# 1_PowerSupply.net
KiCad netlist of a schematic drawn in Altium Designer
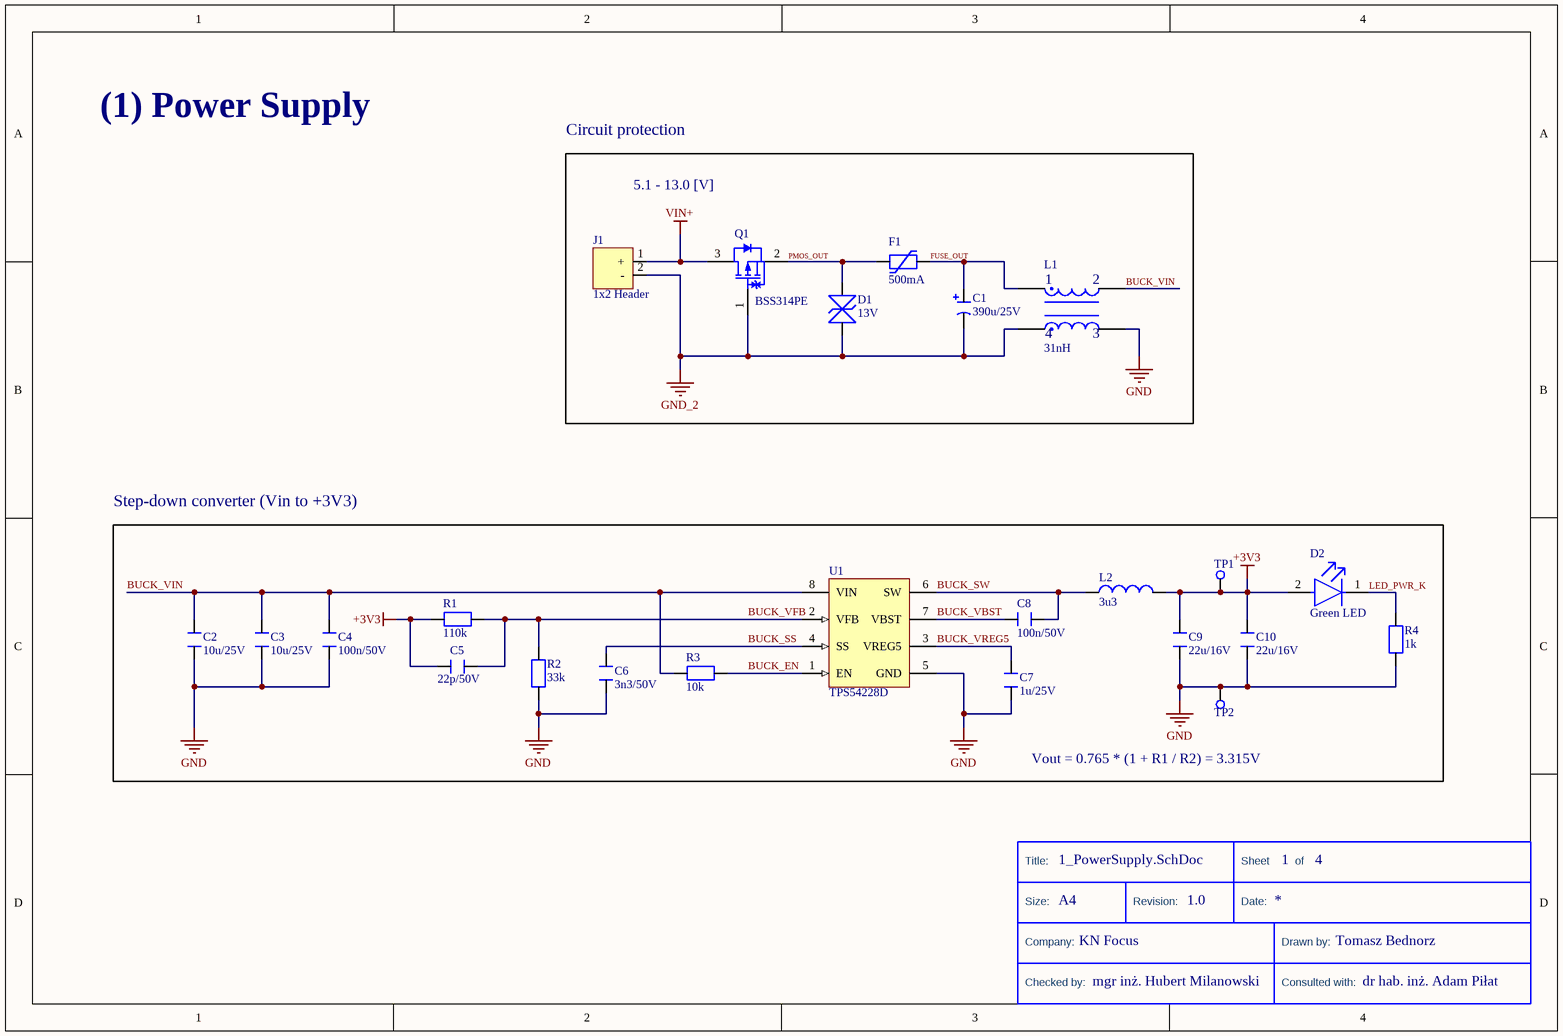
[diagram p0: 1_PowerSupply.SchDoc]

(export (version "E")
  (design (tool "Eeschema 10.0.6"))
  (components
    (comp (ref "C1")
      (value "390u/25V")
      (footprint "CAP_ELECTROLYTIC D8")
      (description "CAP_ELECTROLYTIC D8")
      (libsource (lib "SymbolLib") (part "CAP_ELECTROLYTIC D8"))
    )
    (comp (ref "C2")
      (value "10u/25V")
      (footprint "CAP_1206")
      (description "Generic 1206/3216 capacitor")
      (libsource (lib "SymbolLib") (part "CAP_1206"))
    )
    (comp (ref "C3")
      (value "10u/25V")
      (footprint "CAP_1206")
      (description "Generic 1206/3216 capacitor")
      (libsource (lib "SymbolLib") (part "CAP_1206"))
    )
    (comp (ref "C4")
      (value "100n/50V")
      (footprint "CAP_1206")
      (description "Generic 1206/3216 capacitor")
      (libsource (lib "SymbolLib") (part "CAP_1206"))
    )
    (comp (ref "C5")
      (value "22p/50V")
      (footprint "CAP_1206")
      (description "Generic 1206/3216 capacitor")
      (libsource (lib "SymbolLib") (part "CAP_1206"))
    )
    (comp (ref "C6")
      (value "3n3/50V")
      (footprint "CAP_1206")
      (description "Generic 1206/3216 capacitor")
      (libsource (lib "SymbolLib") (part "CAP_1206"))
    )
    (comp (ref "C7")
      (value "1u/25V")
      (footprint "CAP_1206")
      (description "Generic 1206/3216 capacitor")
      (libsource (lib "SymbolLib") (part "CAP_1206"))
    )
    (comp (ref "C8")
      (value "100n/50V")
      (footprint "CAP_1206")
      (description "Generic 1206/3216 capacitor")
      (libsource (lib "SymbolLib") (part "CAP_1206"))
    )
    (comp (ref "C9")
      (value "22u/16V")
      (footprint "CAP_1206")
      (description "Generic 1206/3216 capacitor")
      (libsource (lib "SymbolLib") (part "CAP_1206"))
    )
    (comp (ref "C10")
      (value "22u/16V")
      (footprint "CAP_1206")
      (description "Generic 1206/3216 capacitor")
      (libsource (lib "SymbolLib") (part "CAP_1206"))
    )
    (comp (ref "D1")
      (value "13V")
      (footprint "TVS_Littlefuse")
      (description "TVS Diode TVS_SMAJ13CA  13V Bidirectional")
      (libsource (lib "SymbolLib") (part "TVS_13V"))
    )
    (comp (ref "D2")
      (value "Green LED")
      (footprint "FP-LTST-C150KGKT-MFG")
      (description "LED GREEN CLEAR 1206 SMD")
      (libsource (lib "Altium Content Vault") (part "8706943c75ba83719d021d2fdc84c58"))
    )
    (comp (ref "F1")
      (value "500mA")
      (footprint "Fuse_1210")
      (description "FUSE 500mA/16V")
      (libsource (lib "SymbolLib") (part "FUSE_0ZCH0050FF2G"))
    )
    (comp (ref "J1")
      (value "1x2 Header")
      (footprint "1x2 Header (Terminal Block 5.08mm)")
      (description "1x2 Header, Through Hole(Terminal Block 5.08mm)")
      (libsource (lib "SymbolLib") (part "1x2 Header (Terminal Block 5.08mm)"))
    )
    (comp (ref "L1")
      (value "31nH")
      (footprint "CMC-1206USB")
      (description "31nH @ 100MHz 2 Line Common Mode Choke Surface Mount 37 Ohms @ 100MHz 1A DCR 0.1 Ohms")
      (libsource (lib "SymbolLib") (part "CMC-1206USB"))
    )
    (comp (ref "L2")
      (value "3u3")
      (footprint "IND_DJNR5020-3R3-S")
      (libsource (lib "SymbolLib") (part "IND_DJNR5020-3R3-S"))
    )
    (comp (ref "Q1")
      (value "BSS314PE")
      (footprint "INF-PG-SOT23_N")
      (fields (field (name "MANUFACTURER") "Infineon"))
      (libsource (lib "Altium Content Vault") (part "INF-BSS3XXPE-PG-SOT23-3"))
    )
    (comp (ref "R1")
      (value "110k")
      (footprint "RES_1206")
      (description "Generic 1206/3216 resistor")
      (libsource (lib "SymbolLib") (part "RES_1206"))
    )
    (comp (ref "R2")
      (value "33k")
      (footprint "RES_1206")
      (description "Generic 1206/3216 resistor")
      (libsource (lib "SymbolLib") (part "RES_1206"))
    )
    (comp (ref "R3")
      (value "10k")
      (footprint "RES_1206")
      (description "Generic 1206/3216 resistor")
      (libsource (lib "SymbolLib") (part "RES_1206"))
    )
    (comp (ref "R4")
      (value "1k")
      (footprint "RES_1206")
      (description "Generic 1206/3216 resistor")
      (libsource (lib "SymbolLib") (part "RES_1206"))
    )
    (comp (ref "TP1")
      (value "TestPoint Pad 1.0mmx1.0mm")
      (footprint "TestPoint Pad 1.0mmx1.0mm")
      (libsource (lib "SymbolLib") (part "TestPoint Pad 1.0mmx1.0mm"))
    )
    (comp (ref "TP2")
      (value "TestPoint Pad 1.0mmx1.0mm")
      (footprint "TestPoint Pad 1.0mmx1.0mm")
      (libsource (lib "SymbolLib") (part "TestPoint Pad 1.0mmx1.0mm"))
    )
    (comp (ref "U1")
      (value "TPS54228D")
      (footprint "D0008A_L")
      (fields (field (name "MANUFACTURER") "Texas Instruments"))
      (libsource (lib "Altium Content Vault") (part "TI-TPS54228D8"))
    )
  )
  (nets
    (net (code "1") (name "+3V3") (class "Default")
      (node (ref "C10") (pin "1") (pinfunction "1_1") (pintype "passive"))
      (node (ref "C5") (pin "2") (pinfunction "2_2") (pintype "passive"))
      (node (ref "C9") (pin "1") (pinfunction "1_1") (pintype "passive"))
      (node (ref "D2") (pin "2") (pinfunction "A_2") (pintype "passive"))
      (node (ref "L2") (pin "2") (pinfunction "2_2") (pintype "passive"))
      (node (ref "R1") (pin "2") (pinfunction "2_2") (pintype "passive"))
      (node (ref "TP1") (pin "1") (pinfunction "1_1") (pintype "passive"))
    )
    (net (code "2") (name "/BUCK_EN") (class "Default")
      (node (ref "R3") (pin "1") (pinfunction "1_1") (pintype "passive"))
      (node (ref "U1") (pin "1") (pinfunction "EN_1") (pintype "input"))
    )
    (net (code "3") (name "/BUCK_SS") (class "Default")
      (node (ref "C6") (pin "2") (pinfunction "2_2") (pintype "passive"))
      (node (ref "U1") (pin "4") (pinfunction "SS_4") (pintype "input"))
    )
    (net (code "4") (name "/BUCK_SW") (class "Default")
      (node (ref "C8") (pin "2") (pinfunction "2_2") (pintype "passive"))
      (node (ref "L2") (pin "1") (pinfunction "1_1") (pintype "passive"))
      (node (ref "U1") (pin "6") (pinfunction "SW_6") (pintype "power_in"))
    )
    (net (code "5") (name "/BUCK_VBST") (class "Default")
      (node (ref "C8") (pin "1") (pinfunction "1_1") (pintype "passive"))
      (node (ref "U1") (pin "7") (pinfunction "VBST_7") (pintype "passive"))
    )
    (net (code "6") (name "/BUCK_VFB") (class "Default")
      (node (ref "C5") (pin "1") (pinfunction "1_1") (pintype "passive"))
      (node (ref "R1") (pin "1") (pinfunction "1_1") (pintype "passive"))
      (node (ref "R2") (pin "1") (pinfunction "1_1") (pintype "passive"))
      (node (ref "U1") (pin "2") (pinfunction "VFB_2") (pintype "input"))
    )
    (net (code "7") (name "/BUCK_VIN") (class "Default")
      (node (ref "C2") (pin "2") (pinfunction "2_2") (pintype "passive"))
      (node (ref "C3") (pin "2") (pinfunction "2_2") (pintype "passive"))
      (node (ref "C4") (pin "2") (pinfunction "2_2") (pintype "passive"))
      (node (ref "L1") (pin "2") (pinfunction "2_2") (pintype "passive"))
      (node (ref "R3") (pin "2") (pinfunction "2_2") (pintype "passive"))
      (node (ref "U1") (pin "8") (pinfunction "VIN_8") (pintype "power_in"))
    )
    (net (code "8") (name "/BUCK_VREG5") (class "Default")
      (node (ref "C7") (pin "1") (pinfunction "1_1") (pintype "passive"))
      (node (ref "U1") (pin "3") (pinfunction "VREG5_3") (pintype "power_in"))
    )
    (net (code "9") (name "/FUSE_OUT") (class "Default")
      (node (ref "C1") (pin "2") (pinfunction "2_2") (pintype "passive"))
      (node (ref "F1") (pin "2") (pinfunction "2_2") (pintype "passive"))
      (node (ref "L1") (pin "1") (pinfunction "1_1") (pintype "passive"))
    )
    (net (code "10") (name "/LED_PWR_K") (class "Default")
      (node (ref "D2") (pin "1") (pinfunction "C_1") (pintype "passive"))
      (node (ref "R4") (pin "1") (pinfunction "1_1") (pintype "passive"))
    )
    (net (code "11") (name "/PMOS_OUT") (class "Default")
      (node (ref "D1") (pin "1") (pinfunction "1_1") (pintype "passive"))
      (node (ref "F1") (pin "1") (pinfunction "1_1") (pintype "passive"))
      (node (ref "Q1") (pin "2") (pinfunction "SOURCE_2") (pintype "passive"))
    )
    (net (code "12") (name "GND") (class "Default")
      (node (ref "C10") (pin "2") (pinfunction "2_2") (pintype "passive"))
      (node (ref "C2") (pin "1") (pinfunction "1_1") (pintype "passive"))
      (node (ref "C3") (pin "1") (pinfunction "1_1") (pintype "passive"))
      (node (ref "C4") (pin "1") (pinfunction "1_1") (pintype "passive"))
      (node (ref "C6") (pin "1") (pinfunction "1_1") (pintype "passive"))
      (node (ref "C7") (pin "2") (pinfunction "2_2") (pintype "passive"))
      (node (ref "C9") (pin "2") (pinfunction "2_2") (pintype "passive"))
      (node (ref "L1") (pin "3") (pinfunction "3_3") (pintype "passive"))
      (node (ref "R2") (pin "2") (pinfunction "2_2") (pintype "passive"))
      (node (ref "R4") (pin "2") (pinfunction "2_2") (pintype "passive"))
      (node (ref "TP2") (pin "1") (pinfunction "1_1") (pintype "passive"))
      (node (ref "U1") (pin "5") (pinfunction "GND_5") (pintype "power_in"))
    )
    (net (code "13") (name "GND_2") (class "Default")
      (node (ref "C1") (pin "1") (pinfunction "1_1") (pintype "passive"))
      (node (ref "D1") (pin "2") (pinfunction "2_2") (pintype "passive"))
      (node (ref "J1") (pin "2") (pinfunction "-_2") (pintype "power_in"))
      (node (ref "L1") (pin "4") (pinfunction "4_4") (pintype "passive"))
      (node (ref "Q1") (pin "1") (pinfunction "GATE_1") (pintype "passive"))
    )
    (net (code "14") (name "VIN+") (class "Default")
      (node (ref "J1") (pin "1") (pinfunction "+_1") (pintype "power_in"))
      (node (ref "Q1") (pin "3") (pinfunction "DRAIN_3") (pintype "passive"))
    )
  )
)
